# Control.net
KiCad netlist of a schematic drawn in Altium Designer
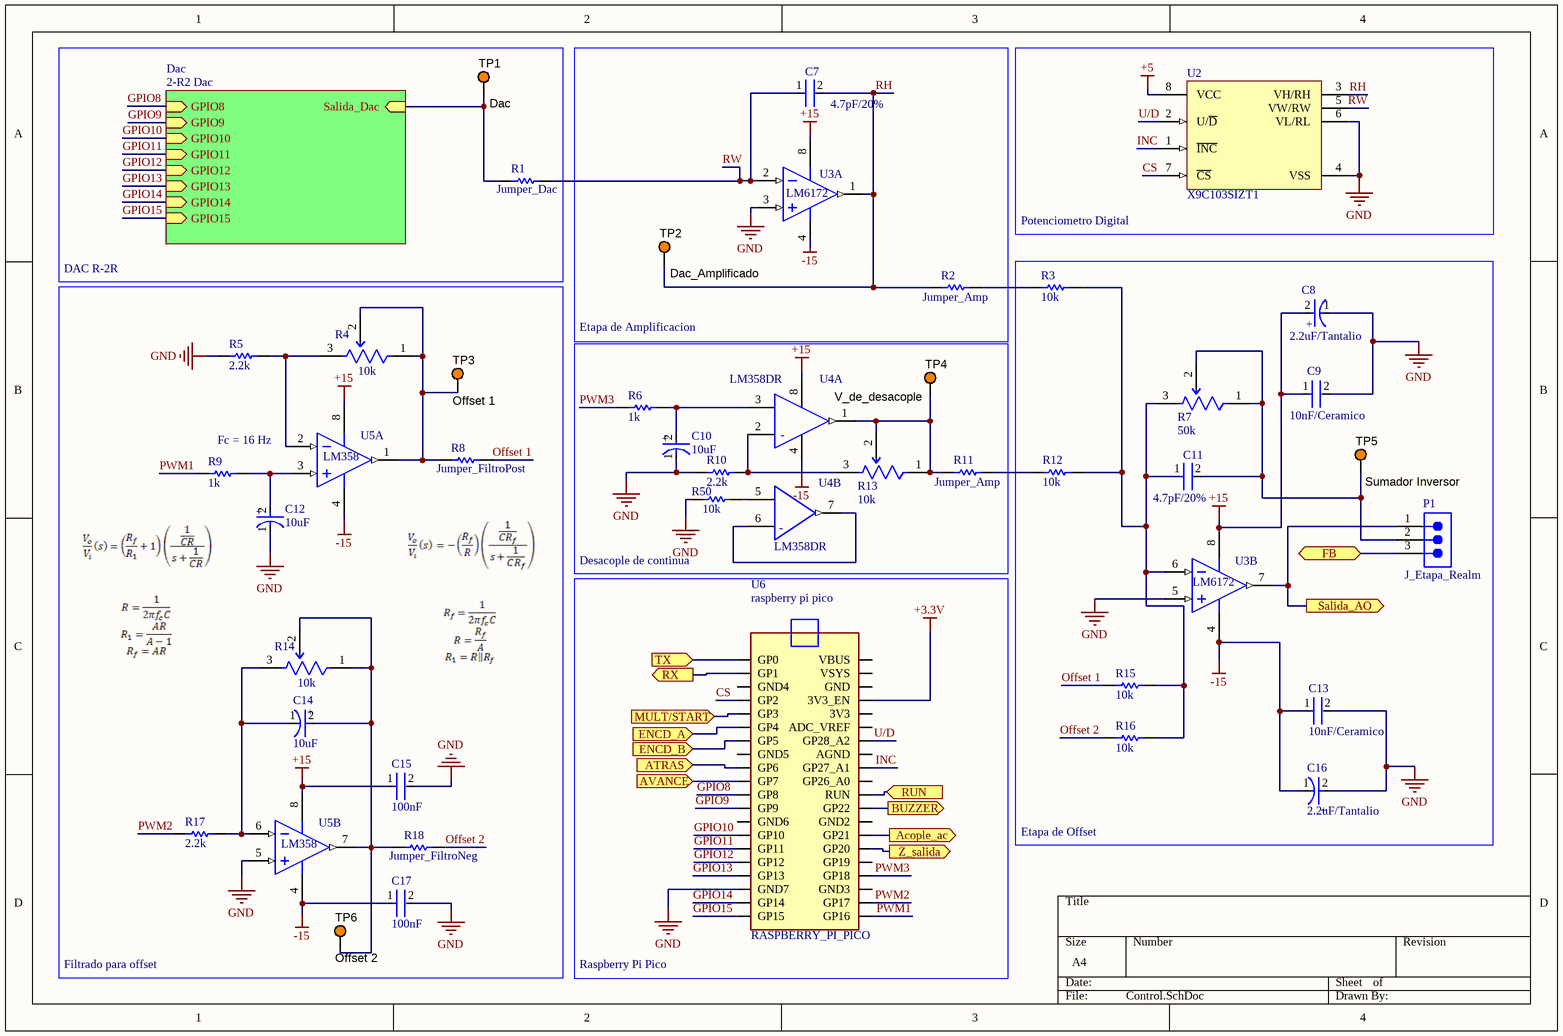
[diagram p0: Control.SchDoc]

(export (version "E")
  (design (tool "Eeschema 10.0.6"))
  (components
    (comp (ref "C7")
      (value "4.7pF/20%")
      (footprint "FP-0805-L_2_01_0_2-W_1_25-IPC_B")
      (description "General Purpose Ceramic Capacitor, 0805, 100nF, 10%, X7R, 15%, 100V")
      (fields (field (name "VOLTAGE") "100V") (field (name "TOLERANCE") "10%"))
      (libsource (lib "Altium Content Vault") (part "b4654b650e69147ec39a6b967a45e02"))
    )
    (comp (ref "C8")
      (value "2.2uF/Tantalio")
      (footprint "FP-T491A225K010AT-MFG")
      (description "CAP TANT 2.2UF 10% 10V 1206")
      (fields (field (name "TOLERANCE") "10%") (field (name "VOLTAGE") "10V"))
      (libsource (lib "Altium Content Vault") (part "a00bbbee19879c290e62620ae7e47b1"))
    )
    (comp (ref "C9")
      (value "10nF/Ceramico")
      (footprint "FP-0805-L_2_01_0_2-W_1_25-IPC_B")
      (description "General Purpose Ceramic Capacitor, 0805, 100nF, 10%, X7R, 15%, 100V")
      (fields (field (name "VOLTAGE") "100V") (field (name "TOLERANCE") "10%"))
      (libsource (lib "Altium Content Vault") (part "b4654b650e69147ec39a6b967a45e02"))
    )
    (comp (ref "C10")
      (value "10uF")
      (footprint "FP-RAD-TH-D_5_0_5-L_11_1-MFG")
      (description "Aluminum Electrolytic Capacitors (Radial Lead Type) 10uF ±20% 63V")
      (fields (field (name "TOLERANCE") "20%") (field (name "VOLTAGE") "63V"))
      (libsource (lib "Altium Content Vault") (part "a00bbbee19879c290e62620ae7e47b1"))
    )
    (comp (ref "C11")
      (value "4.7pF/20%")
      (footprint "FP-0805-L_2_01_0_2-W_1_25-IPC_B")
      (description "General Purpose Ceramic Capacitor, 0805, 100nF, 10%, X7R, 15%, 100V")
      (fields (field (name "VOLTAGE") "100V") (field (name "TOLERANCE") "10%"))
      (libsource (lib "Altium Content Vault") (part "b4654b650e69147ec39a6b967a45e02"))
    )
    (comp (ref "C12")
      (value "10uF")
      (footprint "FP-RAD-TH-D_5_0_5-L_11_1-MFG")
      (description "Aluminum Electrolytic Capacitors (Radial Lead Type) 10uF ±20% 63V")
      (fields (field (name "TOLERANCE") "20%") (field (name "VOLTAGE") "63V"))
      (libsource (lib "Altium Content Vault") (part "a00bbbee19879c290e62620ae7e47b1"))
    )
    (comp (ref "C13")
      (value "10nF/Ceramico")
      (footprint "FP-0805-L_2_01_0_2-W_1_25-IPC_B")
      (description "General Purpose Ceramic Capacitor, 0805, 100nF, 10%, X7R, 15%, 100V")
      (fields (field (name "VOLTAGE") "100V") (field (name "TOLERANCE") "10%"))
      (libsource (lib "Altium Content Vault") (part "b4654b650e69147ec39a6b967a45e02"))
    )
    (comp (ref "C14")
      (value "10uF")
      (footprint "FP-RAD-TH-D_5_0_5-L_11_1-MFG")
      (description "Aluminum Electrolytic Capacitors (Radial Lead Type) 10uF ±20% 63V")
      (fields (field (name "TOLERANCE") "20%") (field (name "VOLTAGE") "63V"))
      (libsource (lib "Altium Content Vault") (part "a00bbbee19879c290e62620ae7e47b1"))
    )
    (comp (ref "C15")
      (value "100nF")
      (footprint "FP-0805-L_2_01_0_2-W_1_25-IPC_B")
      (description "General Purpose Ceramic Capacitor, 0805, 100nF, 10%, X7R, 15%, 100V")
      (fields (field (name "VOLTAGE") "100V") (field (name "TOLERANCE") "10%"))
      (libsource (lib "Altium Content Vault") (part "b4654b650e69147ec39a6b967a45e02"))
    )
    (comp (ref "C16")
      (value "2.2uF/Tantalio")
      (footprint "FP-T491A225K010AT-MFG")
      (description "CAP TANT 2.2UF 10% 10V 1206")
      (fields (field (name "TOLERANCE") "10%") (field (name "VOLTAGE") "10V"))
      (libsource (lib "Altium Content Vault") (part "a00bbbee19879c290e62620ae7e47b1"))
    )
    (comp (ref "C17")
      (value "100nF")
      (footprint "FP-0805-L_2_01_0_2-W_1_25-IPC_B")
      (description "General Purpose Ceramic Capacitor, 0805, 100nF, 10%, X7R, 15%, 100V")
      (fields (field (name "VOLTAGE") "100V") (field (name "TOLERANCE") "10%"))
      (libsource (lib "Altium Content Vault") (part "b4654b650e69147ec39a6b967a45e02"))
    )
    (comp (ref "P1")
      (value "J_Etapa_Realm")
      (footprint "61300311121")
      (libsource (lib "Altium Content Vault") (part "Header_Male_1R_03P"))
    )
    (comp (ref "R1")
      (value "Jumper_Dac")
      (footprint "RESC2013X50X30LL20T20")
      (fields (field (name "MANUFACTURER") "Vishay Dale") (field (name "PART NUMBER") "CRCW08050000Z0EA"))
      (libsource (lib "Altium Content Vault") (part "RES"))
    )
    (comp (ref "R2")
      (value "Jumper_Amp")
      (footprint "RESC2013X50X30LL20T20")
      (fields (field (name "MANUFACTURER") "Vishay Dale") (field (name "PART NUMBER") "CRCW08050000Z0EA"))
      (libsource (lib "Altium Content Vault") (part "RES"))
    )
    (comp (ref "R3")
      (value "10k")
      (footprint "RESC2013X50X30LL20T20")
      (fields (field (name "MANUFACTURER") "Vishay Dale") (field (name "PART NUMBER") "CRCW08050000Z0EA"))
      (libsource (lib "Altium Content Vault") (part "RES"))
    )
    (comp (ref "R4")
      (value "10k")
      (footprint "FP-3296W-MFG")
      (description "TRIMMER 500 OHM 0.5W PC PIN TOP")
      (fields (field (name "TOLERANCE") "10%"))
      (libsource (lib "Altium Content Vault") (part "2dcfd2547301a7d3209a5e99acfd772"))
    )
    (comp (ref "R5")
      (value "2.2k")
      (footprint "RESC2013X50X30LL20T20")
      (fields (field (name "MANUFACTURER") "Vishay Dale") (field (name "PART NUMBER") "CRCW08050000Z0EA"))
      (libsource (lib "Altium Content Vault") (part "RES"))
    )
    (comp (ref "R6")
      (value "1k")
      (footprint "RESC2013X50X30LL20T20")
      (fields (field (name "MANUFACTURER") "Vishay Dale") (field (name "PART NUMBER") "CRCW08050000Z0EA"))
      (libsource (lib "Altium Content Vault") (part "RES"))
    )
    (comp (ref "R7")
      (value "50k")
      (footprint "FP-3296W-MFG")
      (description "TRIMMER 500 OHM 0.5W PC PIN TOP")
      (fields (field (name "TOLERANCE") "10%"))
      (libsource (lib "Altium Content Vault") (part "2dcfd2547301a7d3209a5e99acfd772"))
    )
    (comp (ref "R8")
      (value "Jumper_FiltroPost")
      (footprint "RESC2013X50X30LL20T20")
      (fields (field (name "MANUFACTURER") "Vishay Dale") (field (name "PART NUMBER") "CRCW08050000Z0EA"))
      (libsource (lib "Altium Content Vault") (part "RES"))
    )
    (comp (ref "R9")
      (value "1k")
      (footprint "RESC2013X50X30LL20T20")
      (fields (field (name "MANUFACTURER") "Vishay Dale") (field (name "PART NUMBER") "CRCW08050000Z0EA"))
      (libsource (lib "Altium Content Vault") (part "RES"))
    )
    (comp (ref "R10")
      (value "2.2k")
      (footprint "RESC2013X50X30LL20T20")
      (fields (field (name "MANUFACTURER") "Vishay Dale") (field (name "PART NUMBER") "CRCW08050000Z0EA"))
      (libsource (lib "Altium Content Vault") (part "RES"))
    )
    (comp (ref "R11")
      (value "Jumper_Amp")
      (footprint "RESC2013X50X30LL20T20")
      (fields (field (name "MANUFACTURER") "Vishay Dale") (field (name "PART NUMBER") "CRCW08050000Z0EA"))
      (libsource (lib "Altium Content Vault") (part "RES"))
    )
    (comp (ref "R12")
      (value "10k")
      (footprint "RESC2013X50X30LL20T20")
      (fields (field (name "MANUFACTURER") "Vishay Dale") (field (name "PART NUMBER") "CRCW08050000Z0EA"))
      (libsource (lib "Altium Content Vault") (part "RES"))
    )
    (comp (ref "R13")
      (value "10k")
      (footprint "FP-3296W-MFG")
      (description "TRIMMER 500 OHM 0.5W PC PIN TOP")
      (fields (field (name "TOLERANCE") "10%"))
      (libsource (lib "Altium Content Vault") (part "2dcfd2547301a7d3209a5e99acfd772"))
    )
    (comp (ref "R14")
      (value "10k")
      (footprint "FP-3296W-MFG")
      (description "TRIMMER 500 OHM 0.5W PC PIN TOP")
      (fields (field (name "TOLERANCE") "10%"))
      (libsource (lib "Altium Content Vault") (part "2dcfd2547301a7d3209a5e99acfd772"))
    )
    (comp (ref "R15")
      (value "10k")
      (footprint "RESC2013X50X30LL20T20")
      (fields (field (name "MANUFACTURER") "Vishay Dale") (field (name "PART NUMBER") "CRCW08050000Z0EA"))
      (libsource (lib "Altium Content Vault") (part "RES"))
    )
    (comp (ref "R16")
      (value "10k")
      (footprint "RESC2013X50X30LL20T20")
      (fields (field (name "MANUFACTURER") "Vishay Dale") (field (name "PART NUMBER") "CRCW08050000Z0EA"))
      (libsource (lib "Altium Content Vault") (part "RES"))
    )
    (comp (ref "R17")
      (value "2.2k")
      (footprint "RESC2013X50X30LL20T20")
      (fields (field (name "MANUFACTURER") "Vishay Dale") (field (name "PART NUMBER") "CRCW08050000Z0EA"))
      (libsource (lib "Altium Content Vault") (part "RES"))
    )
    (comp (ref "R18")
      (value "Jumper_FiltroNeg")
      (footprint "RESC2013X50X30LL20T20")
      (fields (field (name "MANUFACTURER") "Vishay Dale") (field (name "PART NUMBER") "CRCW08050000Z0EA"))
      (libsource (lib "Altium Content Vault") (part "RES"))
    )
    (comp (ref "R50")
      (value "10k")
      (footprint "RESC2013X50X30LL20T20")
      (fields (field (name "MANUFACTURER") "Vishay Dale") (field (name "PART NUMBER") "CRCW08050000Z0EA"))
      (libsource (lib "Altium Content Vault") (part "RES"))
    )
    (comp (ref "TP1")
      (value "Dac")
      (footprint "KSTN-5003")
      (description "Test Point, Orange, 1-Pin THD, RoHS")
      (libsource (lib "Altium Content Vault") (part "TESTPOINT_ORANGE"))
    )
    (comp (ref "TP2")
      (value "Dac_Amplificado")
      (footprint "KSTN-5003")
      (description "Test Point, Orange, 1-Pin THD, RoHS")
      (libsource (lib "Altium Content Vault") (part "TESTPOINT_ORANGE"))
    )
    (comp (ref "TP3")
      (value "Offset 1")
      (footprint "KSTN-5003")
      (description "Test Point, Orange, 1-Pin THD, RoHS")
      (libsource (lib "Altium Content Vault") (part "TESTPOINT_ORANGE"))
    )
    (comp (ref "TP4")
      (value "V_de_desacople")
      (footprint "KSTN-5003")
      (description "Test Point, Orange, 1-Pin THD, RoHS")
      (libsource (lib "Altium Content Vault") (part "TESTPOINT_ORANGE"))
    )
    (comp (ref "TP5")
      (value "Sumador Inversor")
      (footprint "KSTN-5003")
      (description "Test Point, Orange, 1-Pin THD, RoHS")
      (libsource (lib "Altium Content Vault") (part "TESTPOINT_ORANGE"))
    )
    (comp (ref "TP6")
      (value "Offset 2")
      (footprint "KSTN-5003")
      (description "Test Point, Orange, 1-Pin THD, RoHS")
      (libsource (lib "Altium Content Vault") (part "TESTPOINT_ORANGE"))
    )
    (comp (ref "U2")
      (value "X9C103SIZT1")
      (footprint "M8_15_MFG")
      (description "X9C103 Series 100 Tap Non Volatile 10 kOhm Digital Potentiometer - SOIC-8")
      (fields (field (name "TOLERANCE") "20%"))
      (libsource (lib "Altium Content Vault") (part "03dc31a757a48b155216eaab65823e2"))
    )
    (comp (ref "U3")
      (value "LM6172")
      (footprint "D0008A_N")
      (description "Dual High Speed, Low Power, Low Distortion Voltage Feedback Amplifiers, 8-pin Narrow SOIC, Pb-Free")
      (fields (field (name "MANUFACTURER") "Texas Instruments"))
      (libsource (lib "Altium Content Vault") (part "AMP-OPA-LM6132-8"))
    )
    (comp (ref "U4")
      (value "LM358DR")
      (footprint "FP-D0008A-MFG")
      (description "IC OPAMP GP 2 CIRCUIT 8SOIC")
      (libsource (lib "Altium Content Vault") (part "0afdfe5f461d2cdd85604ff8654be97"))
    )
    (comp (ref "U5")
      (value "LM358")
      (footprint "ONSC-SOIC-8-751-07_V")
      (fields (field (name "MANUFACTURER") "On Semiconductor") (field (name "PARTNUMBER") "LM358ADR2G"))
      (libsource (lib "Altium Content Vault") (part "ONSC-LM358_NCV2904-8"))
    )
    (comp (ref "U6")
      (value "RASPBERRY_PI_PICO")
      (footprint "RASPBERRY_PI_PICO")
      (fields (field (name "MF") "Raspberry Pi") (field (name "MP") "RASPBERRY PI PICO"))
      (libsource (lib "RASPBERRY_PI_PICO") (part "RASPBERRY_PI_PICO"))
    )
  )
  (nets
    (net (code "1") (name "+3.3V") (class "Default")
      (node (ref "U6") (pin "3V3_EN") (pinfunction "3V3_EN_3V3_EN") (pintype "bidirectional"))
    )
    (net (code "2") (name "+5") (class "Default")
      (node (ref "U2") (pin "8") (pinfunction "VCC_8") (pintype "power_in"))
    )
    (net (code "3") (name "+15") (class "Default")
      (node (ref "C15") (pin "1") (pinfunction "1_1") (pintype "passive"))
      (node (ref "C8") (pin "2") (pinfunction "A_2") (pintype "passive"))
      (node (ref "C9") (pin "1") (pinfunction "1_1") (pintype "passive"))
      (node (ref "U3") (pin "8") (pinfunction "V+_8") (pintype "power_in"))
      (node (ref "U4") (pin "8") (pinfunction "V+_8") (pintype "power_in"))
      (node (ref "U5") (pin "8") (pinfunction "VCC_8") (pintype "power_in"))
    )
    (net (code "4") (name "-15") (class "Default")
      (node (ref "C13") (pin "1") (pinfunction "1_1") (pintype "passive"))
      (node (ref "C16") (pin "1") (pinfunction "C_1") (pintype "passive"))
      (node (ref "C17") (pin "1") (pinfunction "1_1") (pintype "passive"))
      (node (ref "U3") (pin "4") (pinfunction "V-_4") (pintype "power_in"))
      (node (ref "U4") (pin "4") (pinfunction "V-_4") (pintype "power_in"))
      (node (ref "U5") (pin "4") (pinfunction "VEE/GND_4") (pintype "power_in"))
    )
    (net (code "5") (name "/ATRAS") (class "Default")
      (node (ref "U6") (pin "GP6") (pinfunction "GP6_GP6") (pintype "bidirectional"))
    )
    (net (code "6") (name "/AVANCE") (class "Default")
      (node (ref "U6") (pin "GP7") (pinfunction "GP7_GP7") (pintype "bidirectional"))
    )
    (net (code "7") (name "/Acople_ac") (class "Default")
      (node (ref "U6") (pin "GP21") (pinfunction "GP21_GP21") (pintype "bidirectional"))
    )
    (net (code "8") (name "/BUZZER") (class "Default")
      (node (ref "U6") (pin "GP22") (pinfunction "GP22_GP22") (pintype "bidirectional"))
    )
    (net (code "9") (name "/CS") (class "Default")
      (node (ref "U2") (pin "7") (pinfunction "~{CS}_7") (pintype "input"))
      (node (ref "U6") (pin "GP2") (pinfunction "GP2_GP2") (pintype "bidirectional"))
    )
    (net (code "10") (name "/ENCD_A") (class "Default")
      (node (ref "U6") (pin "GP4") (pinfunction "GP4_GP4") (pintype "bidirectional"))
    )
    (net (code "11") (name "/ENCD_B") (class "Default")
      (node (ref "U6") (pin "GP5") (pinfunction "GP5_GP5") (pintype "bidirectional"))
    )
    (net (code "12") (name "/FB") (class "Default")
      (node (ref "P1") (pin "3") (pinfunction "3_3") (pintype "passive"))
    )
    (net (code "13") (name "/GPIO8") (class "Default")
      (node (ref "U6") (pin "GP8") (pinfunction "GP8_GP8") (pintype "bidirectional"))
    )
    (net (code "14") (name "/GPIO9") (class "Default")
      (node (ref "U6") (pin "GP9") (pinfunction "GP9_GP9") (pintype "bidirectional"))
    )
    (net (code "15") (name "/GPIO10") (class "Default")
      (node (ref "U6") (pin "GP10") (pinfunction "GP10_GP10") (pintype "bidirectional"))
    )
    (net (code "16") (name "/GPIO11") (class "Default")
      (node (ref "U6") (pin "GP11") (pinfunction "GP11_GP11") (pintype "bidirectional"))
    )
    (net (code "17") (name "/GPIO12") (class "Default")
      (node (ref "U6") (pin "GP12") (pinfunction "GP12_GP12") (pintype "bidirectional"))
    )
    (net (code "18") (name "/GPIO13") (class "Default")
      (node (ref "U6") (pin "GP13") (pinfunction "GP13_GP13") (pintype "bidirectional"))
    )
    (net (code "19") (name "/GPIO14") (class "Default")
      (node (ref "U6") (pin "GP14") (pinfunction "GP14_GP14") (pintype "bidirectional"))
    )
    (net (code "20") (name "/GPIO15") (class "Default")
      (node (ref "U6") (pin "GP15") (pinfunction "GP15_GP15") (pintype "bidirectional"))
    )
    (net (code "21") (name "/INC") (class "Default")
      (node (ref "U2") (pin "1") (pinfunction "~{INC}_1") (pintype "input"))
      (node (ref "U6") (pin "GP27_A1") (pinfunction "GP27_A1_GP27_A1") (pintype "bidirectional"))
    )
    (net (code "22") (name "/MULT{slash}START") (class "Default")
      (node (ref "U6") (pin "GP3") (pinfunction "GP3_GP3") (pintype "bidirectional"))
    )
    (net (code "23") (name "/Offset 1") (class "Default")
      (node (ref "R15") (pin "1") (pinfunction "1_1") (pintype "passive"))
      (node (ref "R8") (pin "2") (pinfunction "2_2") (pintype "passive"))
    )
    (net (code "24") (name "/Offset 2") (class "Default")
      (node (ref "R16") (pin "1") (pinfunction "1_1") (pintype "passive"))
      (node (ref "R18") (pin "2") (pinfunction "2_2") (pintype "passive"))
    )
    (net (code "25") (name "/PWM1") (class "Default")
      (node (ref "R9") (pin "1") (pinfunction "1_1") (pintype "passive"))
      (node (ref "U6") (pin "GP16") (pinfunction "GP16_GP16") (pintype "bidirectional"))
    )
    (net (code "26") (name "/PWM2") (class "Default")
      (node (ref "R17") (pin "1") (pinfunction "1_1") (pintype "passive"))
      (node (ref "U6") (pin "GP17") (pinfunction "GP17_GP17") (pintype "bidirectional"))
    )
    (net (code "27") (name "/PWM3") (class "Default")
      (node (ref "R6") (pin "1") (pinfunction "1_1") (pintype "passive"))
      (node (ref "U6") (pin "GP18") (pinfunction "GP18_GP18") (pintype "bidirectional"))
    )
    (net (code "28") (name "/RH") (class "Default")
      (node (ref "C7") (pin "2") (pinfunction "2_2") (pintype "passive"))
      (node (ref "R2") (pin "1") (pinfunction "1_1") (pintype "passive"))
      (node (ref "TP2") (pin "1") (pinfunction "1_1") (pintype "passive"))
      (node (ref "U2") (pin "3") (pinfunction "VH/RH_3") (pintype "passive"))
      (node (ref "U3") (pin "1") (pinfunction "OUTA_1") (pintype "output"))
    )
    (net (code "29") (name "/RUN") (class "Default")
      (node (ref "U6") (pin "RUN") (pinfunction "RUN_RUN") (pintype "bidirectional"))
    )
    (net (code "30") (name "/RW") (class "Default")
      (node (ref "C7") (pin "1") (pinfunction "1_1") (pintype "passive"))
      (node (ref "R1") (pin "2") (pinfunction "2_2") (pintype "passive"))
      (node (ref "U2") (pin "5") (pinfunction "VW/RW_5") (pintype "passive"))
      (node (ref "U3") (pin "2") (pinfunction "INA-_2") (pintype "input"))
    )
    (net (code "31") (name "/RX") (class "Default")
      (node (ref "U6") (pin "GP1") (pinfunction "GP1_GP1") (pintype "bidirectional"))
    )
    (net (code "32") (name "/Salida_AO") (class "Default")
      (node (ref "P1") (pin "1") (pinfunction "1_1") (pintype "passive"))
      (node (ref "U3") (pin "7") (pinfunction "OUTB_7") (pintype "output"))
    )
    (net (code "33") (name "/Salida_Dac") (class "Default")
      (node (ref "R1") (pin "1") (pinfunction "1_1") (pintype "passive"))
      (node (ref "TP1") (pin "1") (pinfunction "1_1") (pintype "passive"))
    )
    (net (code "34") (name "/TX") (class "Default")
      (node (ref "U6") (pin "GP0") (pinfunction "GP0_GP0") (pintype "bidirectional"))
    )
    (net (code "35") (name "/U{slash}D") (class "Default")
      (node (ref "U2") (pin "2") (pinfunction "U/~{D}_2") (pintype "input"))
      (node (ref "U6") (pin "GP28_A2") (pinfunction "GP28_A2_GP28_A2") (pintype "bidirectional"))
    )
    (net (code "36") (name "/Z_salida") (class "Default")
      (node (ref "U6") (pin "GP20") (pinfunction "GP20_GP20") (pintype "bidirectional"))
    )
    (net (code "37") (name "GND") (class "Default")
      (node (ref "C10") (pin "1") (pinfunction "C_1") (pintype "passive"))
      (node (ref "C12") (pin "1") (pinfunction "C_1") (pintype "passive"))
      (node (ref "C13") (pin "2") (pinfunction "2_2") (pintype "passive"))
      (node (ref "C15") (pin "2") (pinfunction "2_2") (pintype "passive"))
      (node (ref "C16") (pin "2") (pinfunction "A_2") (pintype "passive"))
      (node (ref "C17") (pin "2") (pinfunction "2_2") (pintype "passive"))
      (node (ref "C8") (pin "1") (pinfunction "C_1") (pintype "passive"))
      (node (ref "C9") (pin "2") (pinfunction "2_2") (pintype "passive"))
      (node (ref "R10") (pin "1") (pinfunction "1_1") (pintype "passive"))
      (node (ref "R5") (pin "1") (pinfunction "1_1") (pintype "passive"))
      (node (ref "R50") (pin "1") (pinfunction "1_1") (pintype "passive"))
      (node (ref "U2") (pin "4") (pinfunction "VSS_4") (pintype "power_in"))
      (node (ref "U2") (pin "6") (pinfunction "VL/RL_6") (pintype "passive"))
      (node (ref "U3") (pin "3") (pinfunction "INA+_3") (pintype "input"))
      (node (ref "U3") (pin "5") (pinfunction "INB+_5") (pintype "input"))
      (node (ref "U5") (pin "5") (pinfunction "INB+_5") (pintype "input"))
      (node (ref "U6") (pin "GND7") (pinfunction "GND7_GND7") (pintype "bidirectional"))
    )
    (net (code "38") (name "Net-(C10-A)") (class "Default")
      (node (ref "C10") (pin "2") (pinfunction "A_2") (pintype "passive"))
      (node (ref "R6") (pin "2") (pinfunction "2_2") (pintype "passive"))
      (node (ref "U4") (pin "3") (pinfunction "IN1+_3") (pintype "tri_state"))
    )
    (net (code "39") (name "Net-(C12-A)") (class "Default")
      (node (ref "C12") (pin "2") (pinfunction "A_2") (pintype "passive"))
      (node (ref "R9") (pin "2") (pinfunction "2_2") (pintype "passive"))
      (node (ref "U5") (pin "3") (pinfunction "INA+_3") (pintype "input"))
    )
    (net (code "40") (name "Net-(C14-A)") (class "Default")
      (node (ref "C14") (pin "2") (pinfunction "A_2") (pintype "passive"))
      (node (ref "R14") (pin "1") (pinfunction "CCW_1") (pintype "passive"))
      (node (ref "R14") (pin "2") (pinfunction "WIPER_2") (pintype "passive"))
      (node (ref "R18") (pin "1") (pinfunction "1_1") (pintype "passive"))
      (node (ref "TP6") (pin "1") (pinfunction "1_1") (pintype "passive"))
      (node (ref "U5") (pin "7") (pinfunction "OUTB_7") (pintype "output"))
    )
    (net (code "41") (name "Net-(C14-C)") (class "Default")
      (node (ref "C14") (pin "1") (pinfunction "C_1") (pintype "passive"))
      (node (ref "R14") (pin "3") (pinfunction "CW_3") (pintype "passive"))
      (node (ref "R17") (pin "2") (pinfunction "2_2") (pintype "passive"))
      (node (ref "U5") (pin "6") (pinfunction "INB-_6") (pintype "input"))
    )
    (net (code "42") (name "Net-(R2-Pad2)") (class "Default")
      (node (ref "R2") (pin "2") (pinfunction "2_2") (pintype "passive"))
      (node (ref "R3") (pin "1") (pinfunction "1_1") (pintype "passive"))
    )
    (net (code "43") (name "Net-(R4-CCW)") (class "Default")
      (node (ref "R4") (pin "1") (pinfunction "CCW_1") (pintype "passive"))
      (node (ref "R4") (pin "2") (pinfunction "WIPER_2") (pintype "passive"))
      (node (ref "R8") (pin "1") (pinfunction "1_1") (pintype "passive"))
      (node (ref "TP3") (pin "1") (pinfunction "1_1") (pintype "passive"))
      (node (ref "U5") (pin "1") (pinfunction "OUTA_1") (pintype "output"))
    )
    (net (code "44") (name "Net-(R4-CW)") (class "Default")
      (node (ref "R4") (pin "3") (pinfunction "CW_3") (pintype "passive"))
      (node (ref "R5") (pin "2") (pinfunction "2_2") (pintype "passive"))
      (node (ref "U5") (pin "2") (pinfunction "INA-_2") (pintype "input"))
    )
    (net (code "45") (name "Net-(R7-CCW)") (class "Default")
      (node (ref "C11") (pin "2") (pinfunction "2_2") (pintype "passive"))
      (node (ref "P1") (pin "2") (pinfunction "2_2") (pintype "passive"))
      (node (ref "R7") (pin "1") (pinfunction "CCW_1") (pintype "passive"))
      (node (ref "R7") (pin "2") (pinfunction "WIPER_2") (pintype "passive"))
      (node (ref "TP5") (pin "1") (pinfunction "1_1") (pintype "passive"))
    )
    (net (code "46") (name "Net-(R7-CW)") (class "Default")
      (node (ref "C11") (pin "1") (pinfunction "1_1") (pintype "passive"))
      (node (ref "R12") (pin "2") (pinfunction "2_2") (pintype "passive"))
      (node (ref "R15") (pin "2") (pinfunction "2_2") (pintype "passive"))
      (node (ref "R16") (pin "2") (pinfunction "2_2") (pintype "passive"))
      (node (ref "R3") (pin "2") (pinfunction "2_2") (pintype "passive"))
      (node (ref "R7") (pin "3") (pinfunction "CW_3") (pintype "passive"))
      (node (ref "U3") (pin "6") (pinfunction "INB-_6") (pintype "input"))
    )
    (net (code "47") (name "Net-(R11-Pad2)") (class "Default")
      (node (ref "R11") (pin "2") (pinfunction "2_2") (pintype "passive"))
      (node (ref "R12") (pin "1") (pinfunction "1_1") (pintype "passive"))
    )
    (net (code "48") (name "Net-(R13-CCW)") (class "Default")
      (node (ref "R11") (pin "1") (pinfunction "1_1") (pintype "passive"))
      (node (ref "R13") (pin "1") (pinfunction "CCW_1") (pintype "passive"))
      (node (ref "R13") (pin "2") (pinfunction "WIPER_2") (pintype "passive"))
      (node (ref "TP4") (pin "1") (pinfunction "1_1") (pintype "passive"))
      (node (ref "U4") (pin "1") (pinfunction "1OUT_1") (pintype "output"))
    )
    (net (code "49") (name "Net-(R13-CW)") (class "Default")
      (node (ref "R10") (pin "2") (pinfunction "2_2") (pintype "passive"))
      (node (ref "R13") (pin "3") (pinfunction "CW_3") (pintype "passive"))
      (node (ref "U4") (pin "2") (pinfunction "IN1-_2") (pintype "tri_state"))
    )
    (net (code "50") (name "Net-(U4B-2OUT)") (class "Default")
      (node (ref "U4") (pin "6") (pinfunction "IN2-_6") (pintype "tri_state"))
      (node (ref "U4") (pin "7") (pinfunction "2OUT_7") (pintype "output"))
    )
    (net (code "51") (name "Net-(U4B-IN2+)") (class "Default")
      (node (ref "R50") (pin "2") (pinfunction "2_2") (pintype "passive"))
      (node (ref "U4") (pin "5") (pinfunction "IN2+_5") (pintype "tri_state"))
    )
    (net (code "52") (name "unconnected-(U6-Pad3V3)") (class "Default")
      (node (ref "U6") (pin "3V3") (pinfunction "3V3_3V3") (pintype "bidirectional"))
    )
    (net (code "53") (name "unconnected-(U6-PadADC_VREF)") (class "Default")
      (node (ref "U6") (pin "ADC_VREF") (pinfunction "ADC_VREF_ADC_VREF") (pintype "bidirectional"))
    )
    (net (code "54") (name "unconnected-(U6-PadAGND)") (class "Default")
      (node (ref "U6") (pin "AGND") (pinfunction "AGND_AGND") (pintype "bidirectional"))
    )
    (net (code "55") (name "unconnected-(U6-PadGND)") (class "Default")
      (node (ref "U6") (pin "GND") (pinfunction "GND_GND") (pintype "bidirectional"))
    )
    (net (code "56") (name "unconnected-(U6-PadGND2)") (class "Default")
      (node (ref "U6") (pin "GND2") (pinfunction "GND2_GND2") (pintype "bidirectional"))
    )
    (net (code "57") (name "unconnected-(U6-PadGND3)") (class "Default")
      (node (ref "U6") (pin "GND3") (pinfunction "GND3_GND3") (pintype "bidirectional"))
    )
    (net (code "58") (name "unconnected-(U6-PadGND4)") (class "Default")
      (node (ref "U6") (pin "GND4") (pinfunction "GND4_GND4") (pintype "bidirectional"))
    )
    (net (code "59") (name "unconnected-(U6-PadGND5)") (class "Default")
      (node (ref "U6") (pin "GND5") (pinfunction "GND5_GND5") (pintype "bidirectional"))
    )
    (net (code "60") (name "unconnected-(U6-PadGND6)") (class "Default")
      (node (ref "U6") (pin "GND6") (pinfunction "GND6_GND6") (pintype "bidirectional"))
    )
    (net (code "61") (name "unconnected-(U6-PadGP19)") (class "Default")
      (node (ref "U6") (pin "GP19") (pinfunction "GP19_GP19") (pintype "bidirectional"))
    )
    (net (code "62") (name "unconnected-(U6-PadGP26_A0)") (class "Default")
      (node (ref "U6") (pin "GP26_A0") (pinfunction "GP26_A0_GP26_A0") (pintype "bidirectional"))
    )
    (net (code "63") (name "unconnected-(U6-PadVBUS)") (class "Default")
      (node (ref "U6") (pin "VBUS") (pinfunction "VBUS_VBUS") (pintype "bidirectional"))
    )
    (net (code "64") (name "unconnected-(U6-PadVSYS)") (class "Default")
      (node (ref "U6") (pin "VSYS") (pinfunction "VSYS_VSYS") (pintype "bidirectional"))
    )
  )
)
